# USB-RS485-unit.net
KiCad netlist of a schematic drawn in Altium Designer
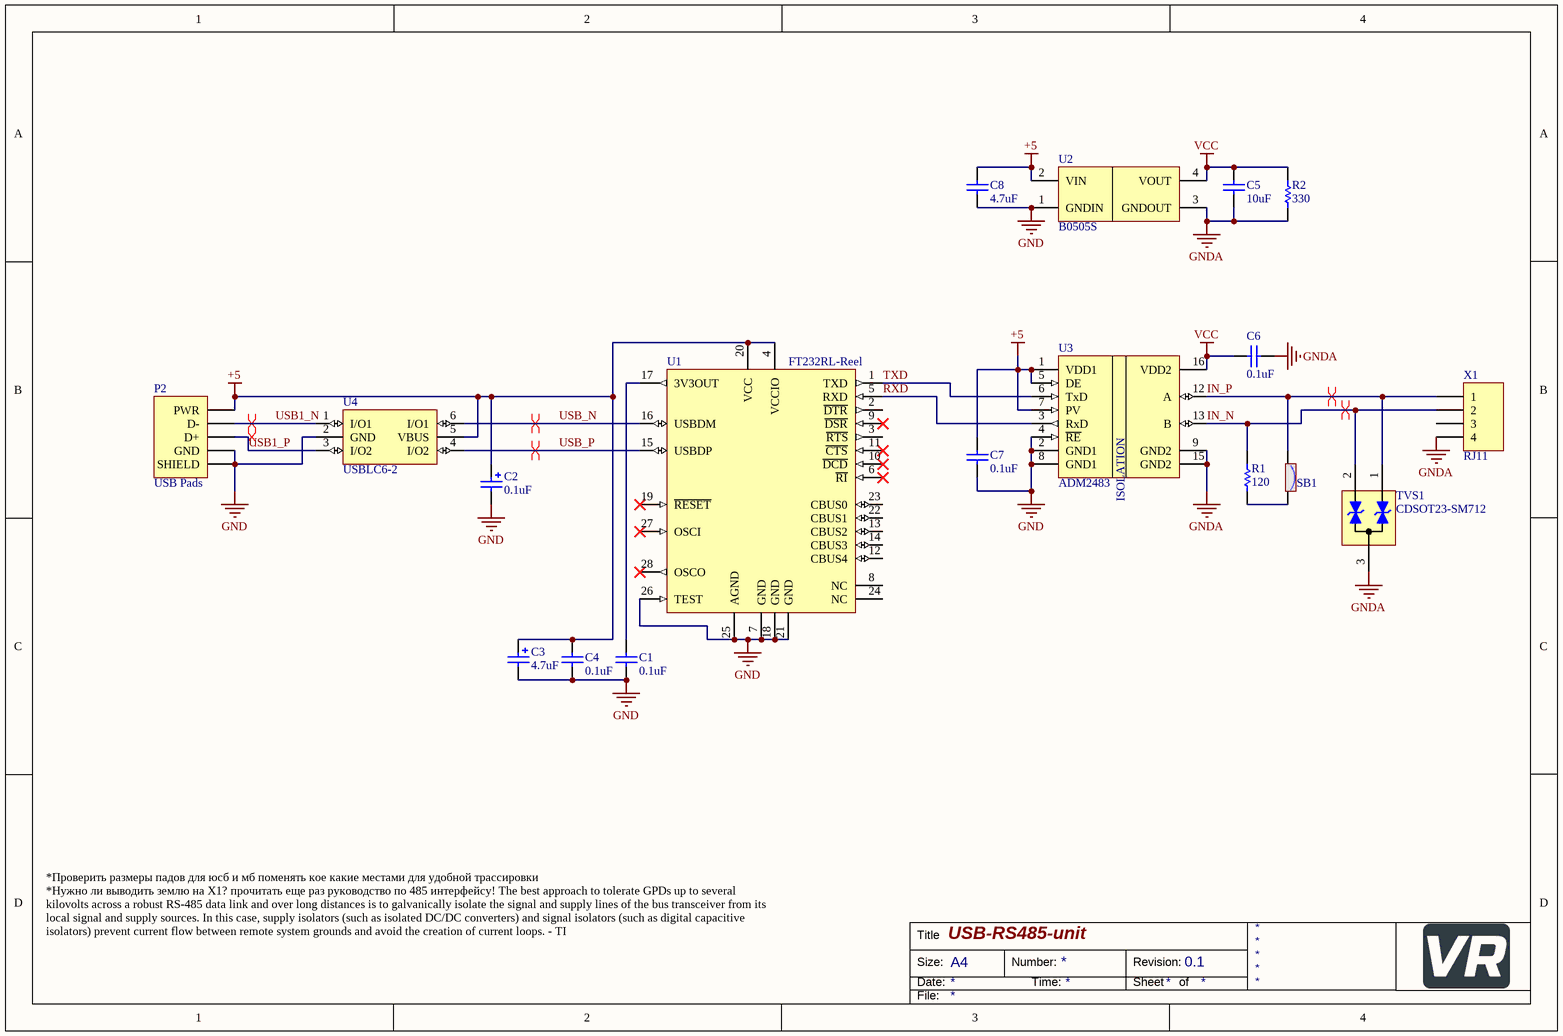
[diagram p0: USB-RS485-unit.SchDoc]

(export (version "E")
  (design (tool "Eeschema 10.0.6"))
  (components
    (comp (ref "C1")
      (value "0.1uF")
      (footprint "C1206")
      (description "Capacitor ceramic SMT")
      (fields
        (field (name "MANUFACTURER_PART_NUMBER") "GRM319R71H104K")
        (field (name "MANUFACTURER") "Murata")
      )
      (libsource (lib "USB-RS485-unit") (part "Cap"))
    )
    (comp (ref "C2")
      (value "0.1uF")
      (footprint "TC3216-1206")
      (description "Polarized Capacitor SMT")
      (fields
        (field (name "MANUFACTURER") "TECAP")
        (field (name "MANUFACTURER_PART_NUMBER") "TECAP0.1/35VA10")
      )
      (libsource (lib "USB-RS485-unit") (part "Cap Polarized"))
    )
    (comp (ref "C3")
      (value "4.7uF")
      (footprint "TC3216-1206")
      (description "Polarized Capacitor SMT")
      (fields
        (field (name "MANUFACTURER") "TECAP")
        (field (name "MANUFACTURER_PART_NUMBER") "TECAP4.7/10VA10")
      )
      (libsource (lib "USB-RS485-unit") (part "Cap Polarized"))
    )
    (comp (ref "C4")
      (value "0.1uF")
      (footprint "C1206")
      (description "Capacitor ceramic SMT")
      (fields
        (field (name "MANUFACTURER_PART_NUMBER") "GRM319R71H104K")
        (field (name "MANUFACTURER") "Murata")
      )
      (libsource (lib "USB-RS485-unit") (part "Cap"))
    )
    (comp (ref "C5")
      (value "10uF")
      (footprint "C1206")
      (description "Capacitor ceramic SMT")
      (fields
        (field (name "MANUFACTURER_PART_NUMBER") "GRM31A7U3A100JW31D")
        (field (name "MANUFACTURER") "Murata")
      )
      (libsource (lib "USB-RS485-unit") (part "Cap"))
    )
    (comp (ref "C6")
      (value "0.1uF")
      (footprint "C1206")
      (description "Capacitor ceramic SMT")
      (fields
        (field (name "MANUFACTURER_PART_NUMBER") "GRM319R71H104K")
        (field (name "MANUFACTURER") "Murata")
      )
      (libsource (lib "USB-RS485-unit") (part "Cap"))
    )
    (comp (ref "C7")
      (value "0.1uF")
      (footprint "C1206")
      (description "Capacitor ceramic SMT")
      (fields
        (field (name "MANUFACTURER_PART_NUMBER") "GRM319R71H104K")
        (field (name "MANUFACTURER") "Murata")
      )
      (libsource (lib "USB-RS485-unit") (part "Cap"))
    )
    (comp (ref "C8")
      (value "4.7uF")
      (footprint "C1206")
      (description "Capacitor ceramic SMT")
      (fields
        (field (name "MANUFACTURER_PART_NUMBER") "GRM31CR71E475KA88L")
        (field (name "MANUFACTURER") "Murata")
      )
      (libsource (lib "USB-RS485-unit") (part "Cap"))
    )
    (comp (ref "P2")
      (value "USB Pads")
      (footprint "USB soldering pads")
      (description "Pads for soldering USB cable")
      (libsource (lib "USB-RS485-unit") (part "USB pads"))
    )
    (comp (ref "R1")
      (value "120")
      (footprint "RES-0805")
      (description "Rectangular Thick Film Chip Resistor")
      (fields
        (field (name "MANUFACTURER") "Yageo")
        (field (name "MANUFACTURER_PART_NUMBER") "RC0805FR-07120RL")
      )
      (libsource (lib "USB-RS485-unit") (part "Res"))
    )
    (comp (ref "R2")
      (value "330")
      (footprint "RES-0805")
      (description "Rectangular Thick Film Chip Resistor")
      (fields
        (field (name "MANUFACTURER") "Yageo")
        (field (name "MANUFACTURER_PART_NUMBER") "RC0805FR-07330RL")
      )
      (libsource (lib "USB-RS485-unit") (part "Res"))
    )
    (comp (ref "SB1")
      (value "SB_OFF")
      (footprint "SOLDER-BRIDGE-R0603-0R")
      (description "Solder Bridge OFF")
      (libsource (lib "USB-RS485-unit") (part "SB_OFF"))
    )
    (comp (ref "TVS1")
      (value "CDSOT23-SM712")
      (footprint "SOT-23B_N")
      (description "Surface Mount TVS Diode")
      (fields (field (name "MANUFACTURER") "Bourns"))
      (libsource (lib "USB-RS485-unit") (part "CDSOT23-SM712"))
    )
    (comp (ref "U1")
      (value "FT232RL-Reel")
      (footprint "SSOP-28_L")
      (description "USB UART Asynchronous Serial Data Transfer Chip, SSOP-28, Tape and Reel")
      (fields (field (name "MANUFACTURER") "FTDI"))
      (libsource (lib "FTDI Communication UART") (part "FT232RL-Reel"))
    )
    (comp (ref "U2")
      (value "B0505S")
      (footprint "B0505S - horizontal")
      (description "Isolated DC-DC Converter")
      (fields
        (field (name "MANUFACTURER_PART_NUMBER") "B0505S-1WR2")
        (field (name "MANUFACTURER") "Mornsun Power")
      )
      (libsource (lib "USB-RS485-unit") (part "B0505S"))
    )
    (comp (ref "U3")
      (value "ADM2483")
      (footprint "SOL-16 Wide")
      (description "Half-Duplex, Isolated RS-485 Transceiver")
      (fields
        (field (name "MANUFACTURER_PART_NUMBER") "ADM2483BRWZ-REEL")
        (field (name "MANUFACTURER") "STMICROELECTRONICS")
      )
      (libsource (lib "USB-RS485-unit") (part "ADM2483"))
    )
    (comp (ref "U4")
      (value "USBLC6-2")
      (footprint "SOT23-6")
      (description "Quad Bidir ESD protection")
      (fields
        (field (name "MANUFACTURER") "STMICROELECTRONICS")
        (field (name "MANUFACTURER_PART_NUMBER") "USBLC6-2SC6")
      )
      (libsource (lib "USB-RS485-unit") (part "USBLC6-2"))
    )
    (comp (ref "X1")
      (value "RJ11")
      (footprint "RJ11")
      (description "RJ-11 Connector, 4-Pin")
      (fields
        (field (name "MANUFACTURER_PART_NUMBER") "DS1132-S40BPX")
        (field (name "MANUFACTURER") "Connfly")
      )
      (libsource (lib "USB-RS485-unit") (part "RJ11"))
    )
  )
  (nets
    (net (code "1") (name "+5") (class "Default")
      (node (ref "C2") (pin "1") (pinfunction "1_1") (pintype "passive"))
      (node (ref "C3") (pin "1") (pinfunction "1_1") (pintype "passive"))
      (node (ref "C4") (pin "2") (pinfunction "2_2") (pintype "passive"))
      (node (ref "C7") (pin "2") (pinfunction "2_2") (pintype "passive"))
      (node (ref "C8") (pin "2") (pinfunction "2_2") (pintype "passive"))
      (node (ref "P2") (pin "1") (pinfunction "PWR_1") (pintype "passive"))
      (node (ref "U1") (pin "20") (pinfunction "VCC_20") (pintype "power_in"))
      (node (ref "U1") (pin "4") (pinfunction "VCCIO_4") (pintype "power_in"))
      (node (ref "U2") (pin "2") (pinfunction "VIN_2") (pintype "power_in"))
      (node (ref "U3") (pin "1") (pinfunction "VDD1_1") (pintype "power_in"))
      (node (ref "U3") (pin "5") (pinfunction "DE_5") (pintype "input"))
      (node (ref "U3") (pin "7") (pinfunction "PV_7") (pintype "input"))
      (node (ref "U4") (pin "5") (pinfunction "VBUS_5") (pintype "power_in"))
    )
    (net (code "2") (name "/IN_N") (class "Default")
      (node (ref "R1") (pin "2") (pinfunction "2_2") (pintype "passive"))
      (node (ref "TVS1") (pin "2") (pintype "passive"))
      (node (ref "U3") (pin "13") (pinfunction "B_13") (pintype "bidirectional"))
      (node (ref "X1") (pin "2") (pinfunction "2_2") (pintype "passive"))
    )
    (net (code "3") (name "/IN_P") (class "Default")
      (node (ref "SB1") (pin "1") (pinfunction "1_1") (pintype "passive"))
      (node (ref "TVS1") (pin "1") (pintype "passive"))
      (node (ref "U3") (pin "12") (pinfunction "A_12") (pintype "bidirectional"))
      (node (ref "X1") (pin "1") (pinfunction "1_1") (pintype "passive"))
    )
    (net (code "4") (name "/RXD") (class "Default")
      (node (ref "U1") (pin "5") (pinfunction "RXD_5") (pintype "input"))
      (node (ref "U3") (pin "3") (pinfunction "RxD_3") (pintype "output"))
    )
    (net (code "5") (name "/TXD") (class "Default")
      (node (ref "U1") (pin "1") (pinfunction "TXD_1") (pintype "output"))
      (node (ref "U3") (pin "6") (pinfunction "TxD_6") (pintype "input"))
    )
    (net (code "6") (name "/USB1_N") (class "Default")
      (node (ref "P2") (pin "2") (pinfunction "D-_2") (pintype "passive"))
      (node (ref "U4") (pin "1") (pinfunction "I/O1_1") (pintype "bidirectional"))
    )
    (net (code "7") (name "/USB1_P") (class "Default")
      (node (ref "P2") (pin "3") (pinfunction "D+_3") (pintype "passive"))
      (node (ref "U4") (pin "3") (pinfunction "I/O2_3") (pintype "bidirectional"))
    )
    (net (code "8") (name "/USB_N") (class "Default")
      (node (ref "U1") (pin "16") (pinfunction "USBDM_16") (pintype "bidirectional"))
      (node (ref "U4") (pin "6") (pinfunction "I/O1_6") (pintype "bidirectional"))
    )
    (net (code "9") (name "/USB_P") (class "Default")
      (node (ref "U1") (pin "15") (pinfunction "USBDP_15") (pintype "bidirectional"))
      (node (ref "U4") (pin "4") (pinfunction "I/O2_4") (pintype "bidirectional"))
    )
    (net (code "10") (name "GND") (class "Default")
      (node (ref "C1") (pin "1") (pinfunction "1_1") (pintype "passive"))
      (node (ref "C2") (pin "2") (pinfunction "2_2") (pintype "passive"))
      (node (ref "C3") (pin "2") (pinfunction "2_2") (pintype "passive"))
      (node (ref "C4") (pin "1") (pinfunction "1_1") (pintype "passive"))
      (node (ref "C7") (pin "1") (pinfunction "1_1") (pintype "passive"))
      (node (ref "C8") (pin "1") (pinfunction "1_1") (pintype "passive"))
      (node (ref "P2") (pin "4") (pinfunction "GND_4") (pintype "passive"))
      (node (ref "P2") (pin "5") (pinfunction "SHIELD_5") (pintype "passive"))
      (node (ref "U1") (pin "18") (pinfunction "GND_18") (pintype "power_in"))
      (node (ref "U1") (pin "21") (pinfunction "GND_21") (pintype "power_in"))
      (node (ref "U1") (pin "25") (pinfunction "AGND_25") (pintype "power_in"))
      (node (ref "U1") (pin "26") (pinfunction "TEST_26") (pintype "input"))
      (node (ref "U1") (pin "7") (pinfunction "GND_7") (pintype "power_in"))
      (node (ref "U2") (pin "1") (pinfunction "GNDIN_1") (pintype "power_in"))
      (node (ref "U3") (pin "2") (pinfunction "GND1_2") (pintype "power_in"))
      (node (ref "U3") (pin "4") (pinfunction "~{RE}_4") (pintype "input"))
      (node (ref "U3") (pin "8") (pinfunction "GND1_8") (pintype "power_in"))
      (node (ref "U4") (pin "2") (pinfunction "GND_2") (pintype "power_in"))
    )
    (net (code "11") (name "GNDA") (class "Default")
      (node (ref "C5") (pin "1") (pinfunction "1_1") (pintype "passive"))
      (node (ref "C6") (pin "1") (pinfunction "1_1") (pintype "passive"))
      (node (ref "R2") (pin "1") (pinfunction "1_1") (pintype "passive"))
      (node (ref "TVS1") (pin "3") (pintype "passive"))
      (node (ref "U2") (pin "3") (pinfunction "GNDOUT_3") (pintype "power_in"))
      (node (ref "U3") (pin "15") (pinfunction "GND2_15") (pintype "power_in"))
      (node (ref "U3") (pin "9") (pinfunction "GND2_9") (pintype "power_in"))
      (node (ref "X1") (pin "4") (pinfunction "4_4") (pintype "passive"))
    )
    (net (code "12") (name "Net-(R1-Pad1)") (class "Default")
      (node (ref "R1") (pin "1") (pinfunction "1_1") (pintype "passive"))
      (node (ref "SB1") (pin "2") (pinfunction "2_2") (pintype "passive"))
    )
    (net (code "13") (name "Net-(U1-3V3OUT)") (class "Default")
      (node (ref "C1") (pin "2") (pinfunction "2_2") (pintype "passive"))
      (node (ref "U1") (pin "17") (pinfunction "3V3OUT_17") (pintype "output"))
    )
    (net (code "14") (name "VCC") (class "Default")
      (node (ref "C5") (pin "2") (pinfunction "2_2") (pintype "passive"))
      (node (ref "C6") (pin "2") (pinfunction "2_2") (pintype "passive"))
      (node (ref "R2") (pin "2") (pinfunction "2_2") (pintype "passive"))
      (node (ref "U2") (pin "4") (pinfunction "VOUT_4") (pintype "power_in"))
      (node (ref "U3") (pin "16") (pinfunction "VDD2_16") (pintype "power_in"))
    )
    (net (code "15") (name "unconnected-(U1-CBUS0-Pad23)") (class "Default")
      (node (ref "U1") (pin "23") (pinfunction "CBUS0_23") (pintype "bidirectional"))
    )
    (net (code "16") (name "unconnected-(U1-CBUS1-Pad22)") (class "Default")
      (node (ref "U1") (pin "22") (pinfunction "CBUS1_22") (pintype "bidirectional"))
    )
    (net (code "17") (name "unconnected-(U1-CBUS2-Pad13)") (class "Default")
      (node (ref "U1") (pin "13") (pinfunction "CBUS2_13") (pintype "bidirectional"))
    )
    (net (code "18") (name "unconnected-(U1-CBUS3-Pad14)") (class "Default")
      (node (ref "U1") (pin "14") (pinfunction "CBUS3_14") (pintype "bidirectional"))
    )
    (net (code "19") (name "unconnected-(U1-CBUS4-Pad12)") (class "Default")
      (node (ref "U1") (pin "12") (pinfunction "CBUS4_12") (pintype "bidirectional"))
    )
    (net (code "20") (name "unconnected-(U1-NC-Pad8)") (class "Default")
      (node (ref "U1") (pin "8") (pinfunction "NC_8") (pintype "passive"))
    )
    (net (code "21") (name "unconnected-(U1-NC-Pad24)") (class "Default")
      (node (ref "U1") (pin "24") (pinfunction "NC_24") (pintype "passive"))
    )
    (net (code "22") (name "unconnected-(U1-OSCI-Pad27)") (class "Default")
      (node (ref "U1") (pin "27") (pinfunction "OSCI_27") (pintype "input+no_connect"))
    )
    (net (code "23") (name "unconnected-(U1-OSCO-Pad28)") (class "Default")
      (node (ref "U1") (pin "28") (pinfunction "OSCO_28") (pintype "output+no_connect"))
    )
    (net (code "24") (name "unconnected-(U1-~{CTS}-Pad11)") (class "Default")
      (node (ref "U1") (pin "11") (pinfunction "~{CTS}_11") (pintype "input+no_connect"))
    )
    (net (code "25") (name "unconnected-(U1-~{DCD}-Pad10)") (class "Default")
      (node (ref "U1") (pin "10") (pinfunction "~{DCD}_10") (pintype "input+no_connect"))
    )
    (net (code "26") (name "unconnected-(U1-~{DSR}-Pad9)") (class "Default")
      (node (ref "U1") (pin "9") (pinfunction "~{DSR}_9") (pintype "input+no_connect"))
    )
    (net (code "27") (name "unconnected-(U1-~{DTR}-Pad2)") (class "Default")
      (node (ref "U1") (pin "2") (pinfunction "~{DTR}_2") (pintype "output"))
    )
    (net (code "28") (name "unconnected-(U1-~{RESET}-Pad19)") (class "Default")
      (node (ref "U1") (pin "19") (pinfunction "~{RESET}_19") (pintype "input+no_connect"))
    )
    (net (code "29") (name "unconnected-(U1-~{RI}-Pad6)") (class "Default")
      (node (ref "U1") (pin "6") (pinfunction "~{RI}_6") (pintype "input+no_connect"))
    )
    (net (code "30") (name "unconnected-(U1-~{RTS}-Pad3)") (class "Default")
      (node (ref "U1") (pin "3") (pinfunction "~{RTS}_3") (pintype "output"))
    )
    (net (code "31") (name "unconnected-(X1-Pad3)") (class "Default")
      (node (ref "X1") (pin "3") (pinfunction "3_3") (pintype "passive"))
    )
  )
)
